# E-27_Line_Sensor.net
KiCad netlist of a schematic drawn in Altium Designer
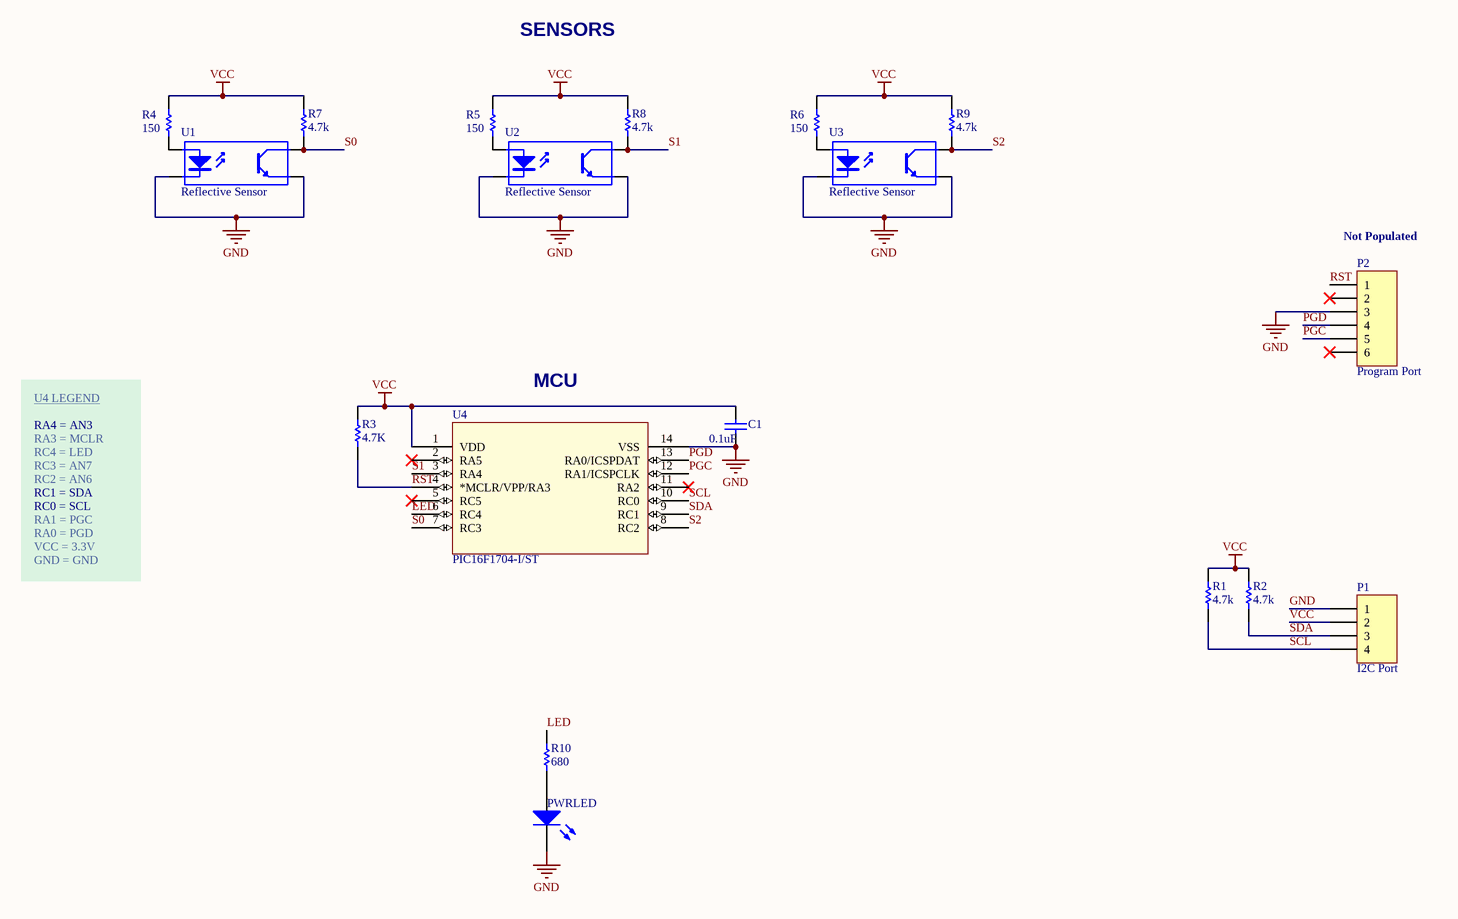
[diagram p0: E-27 Line Sensor.SchDoc]

(export (version "E")
  (design (tool "Eeschema 10.0.6"))
  (components
    (comp (ref "C1")
      (value "0.1uF")
      (footprint "0805 TIGHT")
      (description "Capacitor")
      (fields (field (name "Comment") "18pF") (field (name "PUBLISHER") "Altium Limited"))
      (libsource (lib "SB_Discrete") (part "Cap"))
    )
    (comp (ref "P1")
      (value "I2C Port")
      (footprint "JST-PH 4-pin SMD")
      (description "Header, 4-Pin")
      (fields (field (name "PUBLISHER") "Altium Limited"))
      (libsource (lib "Miscellaneous Connectors") (part "Header 4"))
    )
    (comp (ref "P2")
      (value "Program Port")
      (footprint "Mini Prog header")
      (description "Header, 6-Pin")
      (fields (field (name "PUBLISHER") "Altium Limited"))
      (libsource (lib "Miscellaneous Connectors") (part "Header 6"))
    )
    (comp (ref "PWRLED")
      (value "LED2")
      (footprint "0805 LED - TIGHT")
      (description "Typical RED GaAs LED")
      (fields (field (name "PUBLISHER") "Altium Limited"))
      (libsource (lib "SB_Discrete") (part "LED1"))
    )
    (comp (ref "R1")
      (value "4.7k")
      (footprint "0805 TIGHT")
      (description "Resistor")
      (fields (field (name "Comment") "10kohm") (field (name "PUBLISHER") "Altium Limited"))
      (libsource (lib "SB_Discrete") (part "Res1"))
    )
    (comp (ref "R2")
      (value "4.7k")
      (footprint "0805 TIGHT")
      (description "Resistor")
      (fields (field (name "Comment") "10kohm") (field (name "PUBLISHER") "Altium Limited"))
      (libsource (lib "SB_Discrete") (part "Res1"))
    )
    (comp (ref "R3")
      (value "4.7K")
      (footprint "0805 TIGHT")
      (description "Resistor")
      (fields (field (name "Comment") "Res1") (field (name "PUBLISHER") "Altium Limited"))
      (libsource (lib "SB_Discrete") (part "Res1"))
    )
    (comp (ref "R4")
      (value "150")
      (footprint "0805 TIGHT")
      (description "Resistor")
      (fields (field (name "Comment") "10kohm") (field (name "PUBLISHER") "Altium Limited"))
      (libsource (lib "SB_Discrete") (part "Res1"))
    )
    (comp (ref "R5")
      (value "150")
      (footprint "0805 TIGHT")
      (description "Resistor")
      (fields (field (name "Comment") "10kohm") (field (name "PUBLISHER") "Altium Limited"))
      (libsource (lib "SB_Discrete") (part "Res1"))
    )
    (comp (ref "R6")
      (value "150")
      (footprint "0805 TIGHT")
      (description "Resistor")
      (fields (field (name "Comment") "10kohm") (field (name "PUBLISHER") "Altium Limited"))
      (libsource (lib "SB_Discrete") (part "Res1"))
    )
    (comp (ref "R7")
      (value "4.7k")
      (footprint "0805 TIGHT")
      (description "Resistor")
      (fields (field (name "Comment") "10kohm") (field (name "PUBLISHER") "Altium Limited"))
      (libsource (lib "SB_Discrete") (part "Res1"))
    )
    (comp (ref "R8")
      (value "4.7k")
      (footprint "0805 TIGHT")
      (description "Resistor")
      (fields (field (name "Comment") "10kohm") (field (name "PUBLISHER") "Altium Limited"))
      (libsource (lib "SB_Discrete") (part "Res1"))
    )
    (comp (ref "R9")
      (value "4.7k")
      (footprint "0805 TIGHT")
      (description "Resistor")
      (fields (field (name "Comment") "10kohm") (field (name "PUBLISHER") "Altium Limited"))
      (libsource (lib "SB_Discrete") (part "Res1"))
    )
    (comp (ref "R10")
      (value "680")
      (footprint "0805 TIGHT")
      (description "Resistor")
      (fields (field (name "Comment") "Res1") (field (name "PUBLISHER") "Altium Limited"))
      (libsource (lib "SB_Discrete") (part "Res1"))
    )
    (comp (ref "U1")
      (value "Reflective Sensor")
      (footprint "TCRT5000")
      (description "4-Pin Phototransistor Optocoupler")
      (fields (field (name "PUBLISHER") "Altium Limited"))
      (libsource (lib "Miscellaneous Devices") (part "Optoisolator1"))
    )
    (comp (ref "U2")
      (value "Reflective Sensor")
      (footprint "TCRT5000")
      (description "4-Pin Phototransistor Optocoupler")
      (fields (field (name "PUBLISHER") "Altium Limited"))
      (libsource (lib "Miscellaneous Devices") (part "Optoisolator1"))
    )
    (comp (ref "U3")
      (value "Reflective Sensor")
      (footprint "TCRT5000")
      (description "4-Pin Phototransistor Optocoupler")
      (fields (field (name "PUBLISHER") "Altium Limited"))
      (libsource (lib "Miscellaneous Devices") (part "Optoisolator1"))
    )
    (comp (ref "U4")
      (value "PIC16F1704-I/ST")
      (footprint "TSSOP14")
      (libsource (lib "SB_Engineered_Components") (part "PIC16F1503"))
    )
  )
  (nets
    (net (code "1") (name "/LED") (class "Default")
      (node (ref "R10") (pin "2") (pinfunction "2_2") (pintype "passive"))
      (node (ref "U4") (pin "6") (pinfunction "RC4_6") (pintype "bidirectional"))
    )
    (net (code "2") (name "/PGC") (class "Default")
      (node (ref "P2") (pin "5") (pinfunction "5_5") (pintype "passive"))
      (node (ref "U4") (pin "12") (pinfunction "RA1/ICSPCLK_12") (pintype "bidirectional"))
    )
    (net (code "3") (name "/PGD") (class "Default")
      (node (ref "P2") (pin "4") (pinfunction "4_4") (pintype "passive"))
      (node (ref "U4") (pin "13") (pinfunction "RA0/ICSPDAT_13") (pintype "bidirectional"))
    )
    (net (code "4") (name "/RST") (class "Default")
      (node (ref "P2") (pin "1") (pinfunction "1_1") (pintype "passive"))
      (node (ref "R3") (pin "1") (pinfunction "1_1") (pintype "passive"))
      (node (ref "U4") (pin "4") (pinfunction "*MCLR/VPP/RA3_4") (pintype "bidirectional"))
    )
    (net (code "5") (name "/S0") (class "Default")
      (node (ref "R7") (pin "2") (pinfunction "2_2") (pintype "passive"))
      (node (ref "U1") (pin "4") (pinfunction "C_4") (pintype "passive"))
      (node (ref "U4") (pin "7") (pinfunction "RC3_7") (pintype "bidirectional"))
    )
    (net (code "6") (name "/S1") (class "Default")
      (node (ref "R8") (pin "2") (pinfunction "2_2") (pintype "passive"))
      (node (ref "U2") (pin "4") (pinfunction "C_4") (pintype "passive"))
      (node (ref "U4") (pin "3") (pinfunction "RA4_3") (pintype "bidirectional"))
    )
    (net (code "7") (name "/S2") (class "Default")
      (node (ref "R9") (pin "2") (pinfunction "2_2") (pintype "passive"))
      (node (ref "U3") (pin "4") (pinfunction "C_4") (pintype "passive"))
      (node (ref "U4") (pin "8") (pinfunction "RC2_8") (pintype "bidirectional"))
    )
    (net (code "8") (name "/SCL") (class "Default")
      (node (ref "P1") (pin "4") (pinfunction "4_4") (pintype "passive"))
      (node (ref "R1") (pin "2") (pinfunction "2_2") (pintype "passive"))
      (node (ref "U4") (pin "10") (pinfunction "RC0_10") (pintype "bidirectional"))
    )
    (net (code "9") (name "/SDA") (class "Default")
      (node (ref "P1") (pin "3") (pinfunction "3_3") (pintype "passive"))
      (node (ref "R2") (pin "2") (pinfunction "2_2") (pintype "passive"))
      (node (ref "U4") (pin "9") (pinfunction "RC1_9") (pintype "bidirectional"))
    )
    (net (code "10") (name "GND") (class "Default")
      (node (ref "C1") (pin "1") (pinfunction "1_1") (pintype "passive"))
      (node (ref "P1") (pin "1") (pinfunction "1_1") (pintype "passive"))
      (node (ref "P2") (pin "3") (pinfunction "3_3") (pintype "passive"))
      (node (ref "PWRLED") (pin "2") (pinfunction "K_2") (pintype "passive"))
      (node (ref "U1") (pin "2") (pinfunction "K_2") (pintype "passive"))
      (node (ref "U1") (pin "3") (pinfunction "E_3") (pintype "passive"))
      (node (ref "U2") (pin "2") (pinfunction "K_2") (pintype "passive"))
      (node (ref "U2") (pin "3") (pinfunction "E_3") (pintype "passive"))
      (node (ref "U3") (pin "2") (pinfunction "K_2") (pintype "passive"))
      (node (ref "U3") (pin "3") (pinfunction "E_3") (pintype "passive"))
      (node (ref "U4") (pin "14") (pinfunction "VSS_14") (pintype "power_in"))
    )
    (net (code "11") (name "Net-(PWRLED-A)") (class "Default")
      (node (ref "PWRLED") (pin "1") (pinfunction "A_1") (pintype "passive"))
      (node (ref "R10") (pin "1") (pinfunction "1_1") (pintype "passive"))
    )
    (net (code "12") (name "Net-(U1-A)") (class "Default")
      (node (ref "R4") (pin "1") (pinfunction "1_1") (pintype "passive"))
      (node (ref "U1") (pin "1") (pinfunction "A_1") (pintype "passive"))
    )
    (net (code "13") (name "Net-(U2-A)") (class "Default")
      (node (ref "R5") (pin "2") (pinfunction "2_2") (pintype "passive"))
      (node (ref "U2") (pin "1") (pinfunction "A_1") (pintype "passive"))
    )
    (net (code "14") (name "Net-(U3-A)") (class "Default")
      (node (ref "R6") (pin "1") (pinfunction "1_1") (pintype "passive"))
      (node (ref "U3") (pin "1") (pinfunction "A_1") (pintype "passive"))
    )
    (net (code "15") (name "VCC") (class "Default")
      (node (ref "C1") (pin "2") (pinfunction "2_2") (pintype "passive"))
      (node (ref "P1") (pin "2") (pinfunction "2_2") (pintype "passive"))
      (node (ref "R1") (pin "1") (pinfunction "1_1") (pintype "passive"))
      (node (ref "R2") (pin "1") (pinfunction "1_1") (pintype "passive"))
      (node (ref "R3") (pin "2") (pinfunction "2_2") (pintype "passive"))
      (node (ref "R4") (pin "2") (pinfunction "2_2") (pintype "passive"))
      (node (ref "R5") (pin "1") (pinfunction "1_1") (pintype "passive"))
      (node (ref "R6") (pin "2") (pinfunction "2_2") (pintype "passive"))
      (node (ref "R7") (pin "1") (pinfunction "1_1") (pintype "passive"))
      (node (ref "R8") (pin "1") (pinfunction "1_1") (pintype "passive"))
      (node (ref "R9") (pin "1") (pinfunction "1_1") (pintype "passive"))
      (node (ref "U4") (pin "1") (pinfunction "VDD_1") (pintype "power_in"))
    )
    (net (code "16") (name "unconnected-(P2-Pad2)") (class "Default")
      (node (ref "P2") (pin "2") (pinfunction "2_2") (pintype "passive+no_connect"))
    )
    (net (code "17") (name "unconnected-(P2-Pad6)") (class "Default")
      (node (ref "P2") (pin "6") (pinfunction "6_6") (pintype "passive+no_connect"))
    )
    (net (code "18") (name "unconnected-(U4-RA2-Pad11)") (class "Default")
      (node (ref "U4") (pin "11") (pinfunction "RA2_11") (pintype "bidirectional+no_connect"))
    )
    (net (code "19") (name "unconnected-(U4-RA5-Pad2)") (class "Default")
      (node (ref "U4") (pin "2") (pinfunction "RA5_2") (pintype "bidirectional+no_connect"))
    )
    (net (code "20") (name "unconnected-(U4-RC5-Pad5)") (class "Default")
      (node (ref "U4") (pin "5") (pinfunction "RC5_5") (pintype "bidirectional+no_connect"))
    )
  )
)
